# cSLIM_RTC.net
KiCad netlist of a schematic drawn in Altium Designer
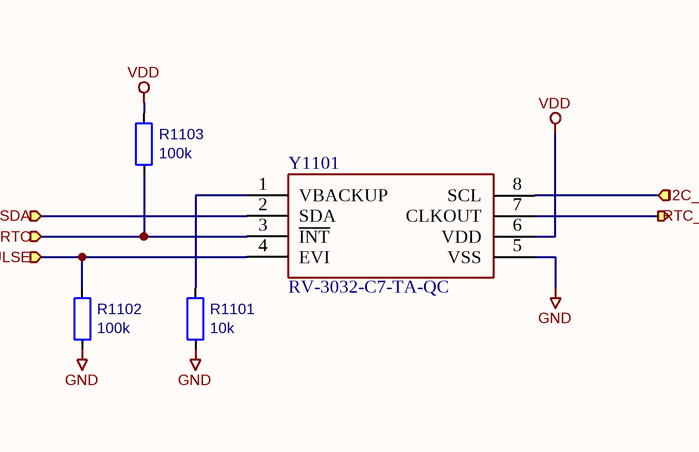
[diagram p0: cSLIM_RTC.SchDoc]

(export (version "E")
  (design (tool "Eeschema 10.0.6"))
  (components
    (comp (ref "R1101") (value "10k") (footprint "RESC1608X55N") (libsource (lib "") (part "R_1")))
    (comp (ref "R1102") (value "100k") (footprint "RESC1608X55N") (libsource (lib "cSLIM-SA") (part "R")))
    (comp (ref "R1103") (value "100k") (footprint "RESC1608X55N") (libsource (lib "cSLIM-SA") (part "R")))
    (comp (ref "Y1101")
      (value "RV-3032-C7-TA-QC")
      (footprint "cSLIM-SA:RV3032C7TAQA")
      (description "Integrated Circuit")
      (libsource (lib "cSLIM-SA") (part "RV-3032-C7-TA-QC"))
    )
  )
  (nets
    (net (code "1") (name "/GPS_TIMEPULSE") (class "Default")
      (node (ref "R1102") (pin "2") (pinfunction "2_2") (pintype "passive"))
      (node (ref "Y1101") (pin "4") (pinfunction "EVI_4") (pintype "passive"))
    )
    (net (code "2") (name "/I2C_SCL") (class "Default")
      (node (ref "Y1101") (pin "8") (pinfunction "SCL_8") (pintype "passive"))
    )
    (net (code "3") (name "/I2C_SDA") (class "Default")
      (node (ref "Y1101") (pin "2") (pinfunction "SDA_2") (pintype "passive"))
    )
    (net (code "4") (name "/RTC_Clockout") (class "Default")
      (node (ref "Y1101") (pin "7") (pinfunction "CLKOUT_7") (pintype "passive"))
    )
    (net (code "5") (name "/nINT_RTC") (class "Default")
      (node (ref "R1103") (pin "1") (pinfunction "1_1") (pintype "passive"))
      (node (ref "Y1101") (pin "3") (pinfunction "~{INT}_3") (pintype "passive"))
    )
    (net (code "6") (name "GND") (class "Default")
      (node (ref "R1101") (pin "2") (pinfunction "2_2") (pintype "passive"))
      (node (ref "R1102") (pin "1") (pinfunction "1_1") (pintype "passive"))
      (node (ref "Y1101") (pin "5") (pinfunction "VSS_5") (pintype "passive"))
    )
    (net (code "7") (name "Net-(Y1101-VBACKUP)") (class "Default")
      (node (ref "R1101") (pin "1") (pinfunction "1_1") (pintype "passive"))
      (node (ref "Y1101") (pin "1") (pinfunction "VBACKUP_1") (pintype "passive"))
    )
    (net (code "8") (name "VDD") (class "Default")
      (node (ref "R1103") (pin "2") (pinfunction "2_2") (pintype "passive"))
      (node (ref "Y1101") (pin "6") (pinfunction "VDD_6") (pintype "passive"))
    )
  )
)
